# atmega16m1-breakout.net
KiCad netlist of a schematic drawn in EAGLE
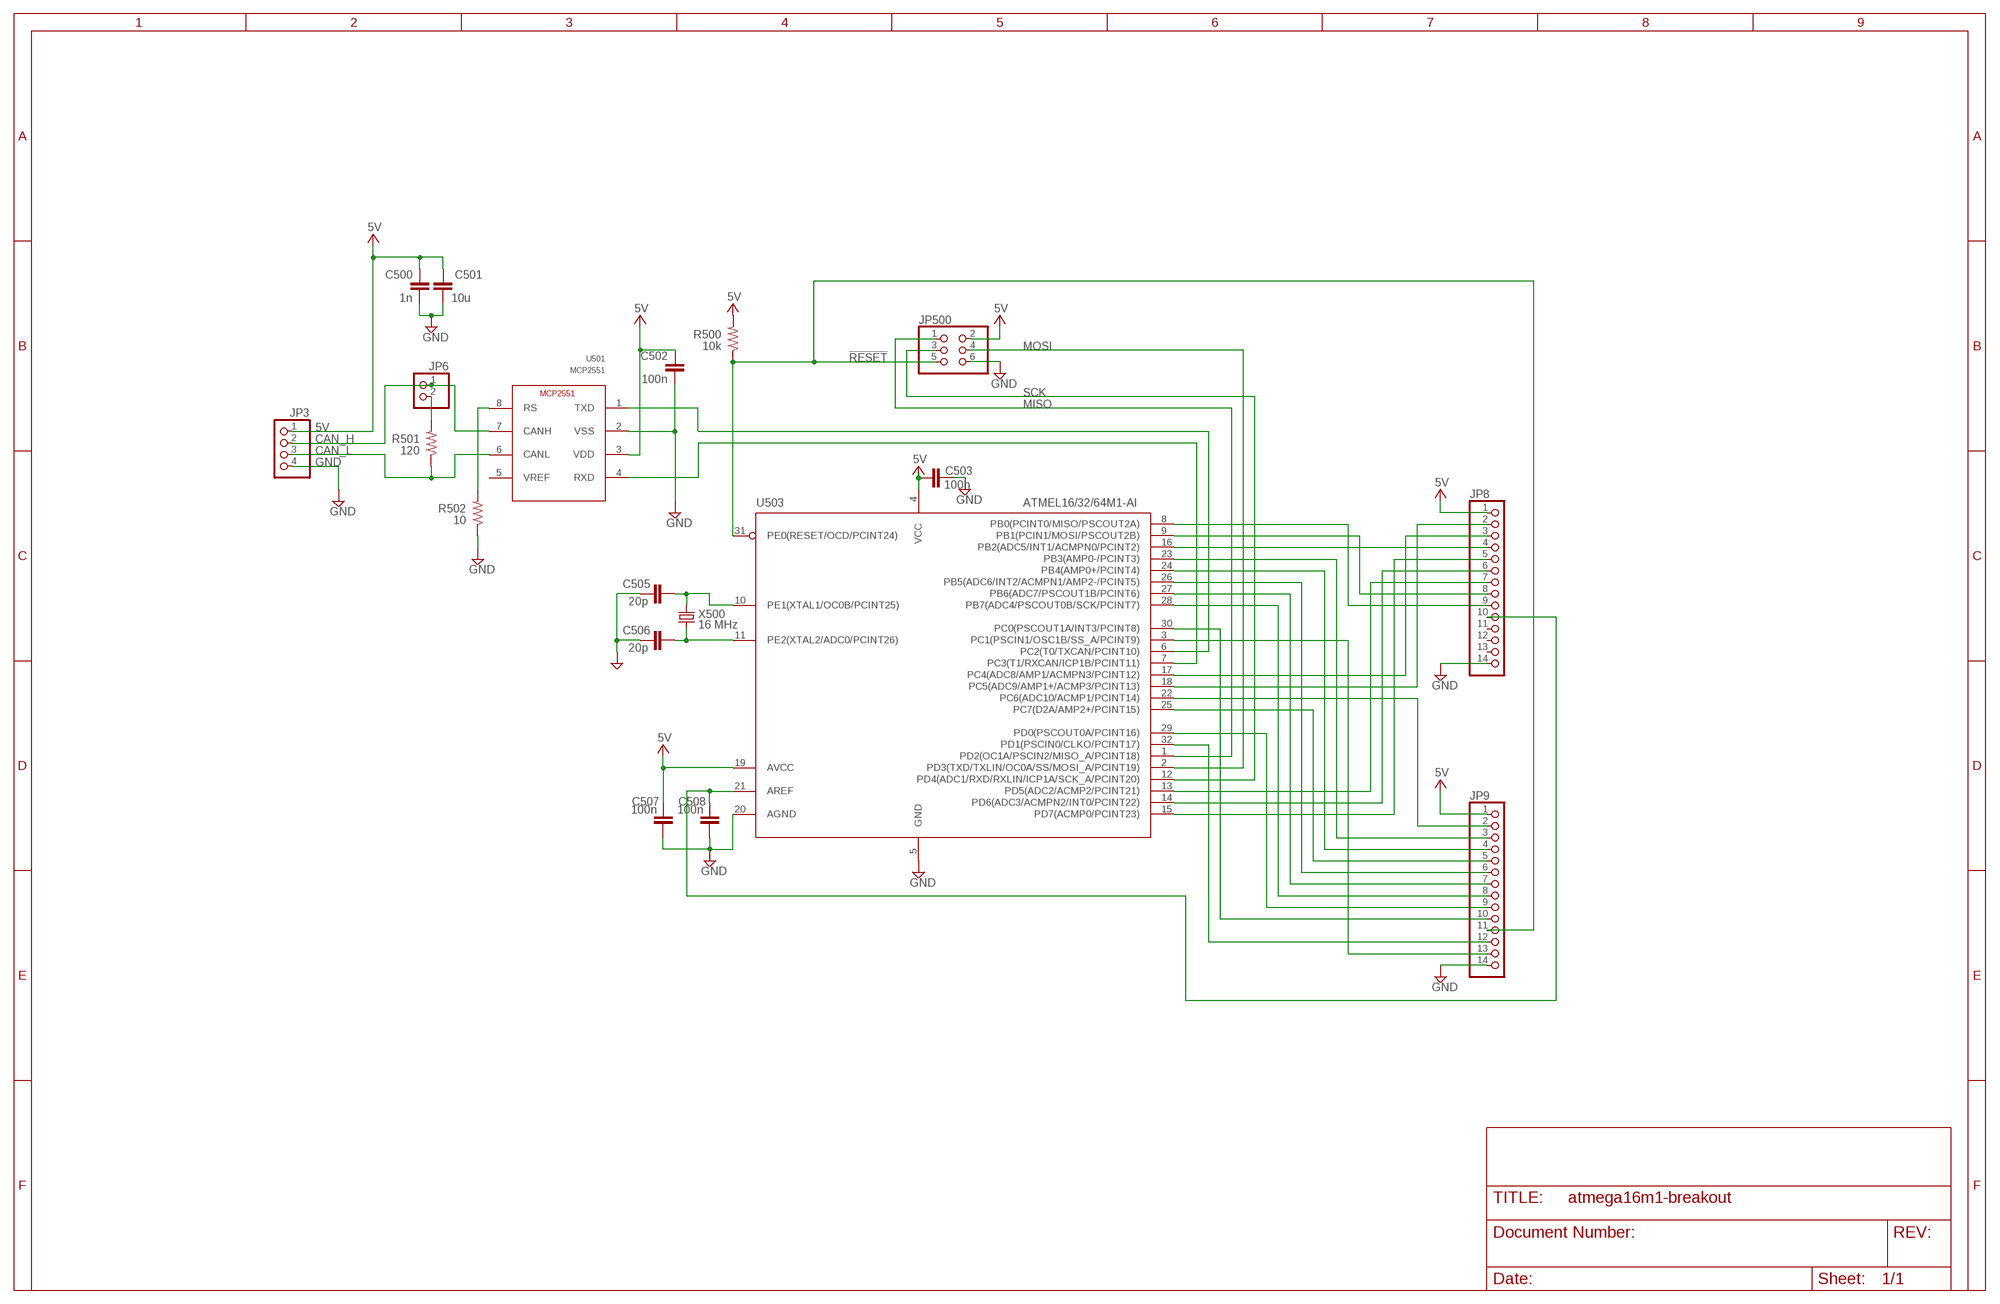
[diagram p0: schematic, sheet 1]

(export (version "E")
  (design (tool "Eeschema 10.0.6"))
  (components
    (comp (ref "C500")
      (value "1n")
      (footprint "eagle-import:0603-B-NOSILK")
      (libsource (lib "eagle-import") (part "C-EU0603-B-NOSILK"))
    )
    (comp (ref "C501")
      (value "10u")
      (footprint "eagle-import:0805-B-NOSILK")
      (libsource (lib "eagle-import") (part "C-EU0805-B-NOSILK"))
    )
    (comp (ref "C502")
      (value "100n")
      (footprint "eagle-import:0603-B-NOSILK")
      (libsource (lib "eagle-import") (part "C-EU0603-B-NOSILK"))
    )
    (comp (ref "C503")
      (value "100n")
      (footprint "eagle-import:0603-B-NOSILK")
      (libsource (lib "eagle-import") (part "C-EU0603-B-NOSILK"))
    )
    (comp (ref "C505")
      (value "20p")
      (footprint "eagle-import:0603-B-NOSILK")
      (libsource (lib "eagle-import") (part "C-EU0603-B-NOSILK"))
    )
    (comp (ref "C506")
      (value "20p")
      (footprint "eagle-import:0603-B-NOSILK")
      (libsource (lib "eagle-import") (part "C-EU0603-B-NOSILK"))
    )
    (comp (ref "C507")
      (value "100n")
      (footprint "eagle-import:0603-B-NOSILK")
      (libsource (lib "eagle-import") (part "C-EU0603-B-NOSILK"))
    )
    (comp (ref "C508")
      (value "100n")
      (footprint "eagle-import:0603-B-NOSILK")
      (libsource (lib "eagle-import") (part "C-EU0603-B-NOSILK"))
    )
    (comp (ref "JP3")
      (value "PINHD-1X4")
      (footprint "eagle-import:1X04")
      (libsource (lib "eagle-import") (part "PINHD-1X4"))
    )
    (comp (ref "JP6")
      (value "PINHD-1X2")
      (footprint "eagle-import:1X02")
      (libsource (lib "eagle-import") (part "PINHD-1X2"))
    )
    (comp (ref "JP8")
      (value "PINHD-1X14")
      (footprint "eagle-import:1X14")
      (libsource (lib "eagle-import") (part "PINHD-1X14"))
    )
    (comp (ref "JP9")
      (value "PINHD-1X14")
      (footprint "eagle-import:1X14")
      (libsource (lib "eagle-import") (part "PINHD-1X14"))
    )
    (comp (ref "JP500")
      (value "PINHD-2X3")
      (footprint "eagle-import:2X03")
      (libsource (lib "eagle-import") (part "PINHD-2X3"))
    )
    (comp (ref "R500")
      (value "10k")
      (footprint "eagle-import:0603-B-NOSILK")
      (libsource (lib "eagle-import") (part "R-US_0603-B-NOSILK"))
    )
    (comp (ref "R501")
      (value "120")
      (footprint "eagle-import:0603-B-NOSILK")
      (libsource (lib "eagle-import") (part "R-US_0603-B-NOSILK"))
    )
    (comp (ref "R502")
      (value "10")
      (footprint "eagle-import:0603-B-NOSILK")
      (libsource (lib "eagle-import") (part "R-US_0603-B-NOSILK"))
    )
    (comp (ref "U501")
      (value "MCP2551")
      (footprint "eagle-import:SO08")
      (libsource (lib "eagle-import") (part "MCP2551"))
    )
    (comp (ref "U503")
      (value "ATMEL16/32/64M1-AI")
      (footprint "eagle-import:TQFP32-08")
      (fields (field (name "MPN") "ATMEGA8-16AU"))
      (libsource (lib "eagle-import") (part "ATMEL16/32/64M1-AZ"))
    )
    (comp (ref "X500")
      (value "16 MHz")
      (footprint "eagle-import:ABM3")
      (libsource (lib "eagle-import") (part "CRYSTALABM3"))
    )
  )
  (nets
    (net (code "1") (name "/CAN_H") (class "Default")
      (node (ref "JP3") (pin "2") (pinfunction "2_2") (pintype "passive"))
      (node (ref "JP6") (pin "1") (pinfunction "1_1") (pintype "passive"))
      (node (ref "U501") (pin "7") (pinfunction "CANH_7") (pintype "bidirectional"))
    )
    (net (code "2") (name "/CAN_L") (class "Default")
      (node (ref "JP3") (pin "3") (pinfunction "3_3") (pintype "passive"))
      (node (ref "R501") (pin "1") (pinfunction "1_1") (pintype "passive"))
      (node (ref "U501") (pin "6") (pinfunction "CANL_6") (pintype "bidirectional"))
    )
    (net (code "3") (name "/MISO") (class "Default")
      (node (ref "JP500") (pin "1") (pinfunction "1_1") (pintype "passive"))
      (node (ref "U503") (pin "1") (pinfunction "PD2(OC1A/PSCIN2/MISO_A/PCINT18)_1") (pintype "bidirectional"))
    )
    (net (code "4") (name "/MOSI") (class "Default")
      (node (ref "JP500") (pin "4") (pinfunction "4_4") (pintype "passive"))
      (node (ref "U503") (pin "2") (pinfunction "PD3(TXD/TXLIN/OC0A/SS/MOSI_A/PCINT19)_2") (pintype "bidirectional"))
    )
    (net (code "5") (name "/SCK") (class "Default")
      (node (ref "JP500") (pin "3") (pinfunction "3_3") (pintype "passive"))
      (node (ref "U503") (pin "12") (pinfunction "PD4(ADC1/RXD/RXLIN/ICP1A/SCK_A/PCINT20)_12") (pintype "bidirectional"))
    )
    (net (code "6") (name "/~{RESET}") (class "Default")
      (node (ref "JP500") (pin "5") (pinfunction "5_5") (pintype "passive"))
      (node (ref "JP9") (pin "11") (pinfunction "11_11") (pintype "passive"))
      (node (ref "R500") (pin "1") (pinfunction "1_1") (pintype "passive"))
      (node (ref "U503") (pin "31") (pinfunction "PE0(RESET/OCD/PCINT24)_31") (pintype "bidirectional"))
    )
    (net (code "7") (name "5V") (class "Default")
      (node (ref "C500") (pin "1") (pinfunction "1_1") (pintype "passive"))
      (node (ref "C501") (pin "1") (pinfunction "1_1") (pintype "passive"))
      (node (ref "C502") (pin "1") (pinfunction "1_1") (pintype "passive"))
      (node (ref "C503") (pin "2") (pinfunction "2_2") (pintype "passive"))
      (node (ref "C507") (pin "1") (pinfunction "1_1") (pintype "passive"))
      (node (ref "JP3") (pin "1") (pinfunction "1_1") (pintype "passive"))
      (node (ref "JP500") (pin "2") (pinfunction "2_2") (pintype "passive"))
      (node (ref "JP8") (pin "1") (pinfunction "1_1") (pintype "passive"))
      (node (ref "JP9") (pin "1") (pinfunction "1_1") (pintype "passive"))
      (node (ref "R500") (pin "2") (pinfunction "2_2") (pintype "passive"))
      (node (ref "U501") (pin "3") (pinfunction "VDD_3") (pintype "power_in"))
      (node (ref "U503") (pin "19") (pinfunction "AVCC_19") (pintype "power_in"))
      (node (ref "U503") (pin "4") (pinfunction "VCC_4") (pintype "power_in"))
    )
    (net (code "8") (name "GND") (class "Default")
      (node (ref "C500") (pin "2") (pinfunction "2_2") (pintype "passive"))
      (node (ref "C501") (pin "2") (pinfunction "2_2") (pintype "passive"))
      (node (ref "C502") (pin "2") (pinfunction "2_2") (pintype "passive"))
      (node (ref "C503") (pin "1") (pinfunction "1_1") (pintype "passive"))
      (node (ref "C505") (pin "2") (pinfunction "2_2") (pintype "passive"))
      (node (ref "C506") (pin "2") (pinfunction "2_2") (pintype "passive"))
      (node (ref "C507") (pin "2") (pinfunction "2_2") (pintype "passive"))
      (node (ref "C508") (pin "2") (pinfunction "2_2") (pintype "passive"))
      (node (ref "JP3") (pin "4") (pinfunction "4_4") (pintype "passive"))
      (node (ref "JP500") (pin "6") (pinfunction "6_6") (pintype "passive"))
      (node (ref "JP8") (pin "14") (pinfunction "14_14") (pintype "passive"))
      (node (ref "JP9") (pin "14") (pinfunction "14_14") (pintype "passive"))
      (node (ref "R502") (pin "1") (pinfunction "1_1") (pintype "passive"))
      (node (ref "U501") (pin "2") (pinfunction "VSS_2") (pintype "power_in"))
      (node (ref "U503") (pin "20") (pinfunction "AGND_20") (pintype "power_in"))
      (node (ref "U503") (pin "5") (pinfunction "GND_5") (pintype "power_in"))
    )
    (net (code "9") (name "Net-(JP6-Pad2)") (class "Default")
      (node (ref "JP6") (pin "2") (pinfunction "2_2") (pintype "passive"))
      (node (ref "R501") (pin "2") (pinfunction "2_2") (pintype "passive"))
    )
    (net (code "10") (name "Net-(U501-RS)") (class "Default")
      (node (ref "R502") (pin "2") (pinfunction "2_2") (pintype "passive"))
      (node (ref "U501") (pin "8") (pinfunction "RS_8") (pintype "bidirectional"))
    )
    (net (code "11") (name "Net-(U501-RXD)") (class "Default")
      (node (ref "U501") (pin "4") (pinfunction "RXD_4") (pintype "bidirectional"))
      (node (ref "U503") (pin "7") (pinfunction "PC3(T1/RXCAN/ICP1B/PCINT11)_7") (pintype "bidirectional"))
    )
    (net (code "12") (name "Net-(U501-TXD)") (class "Default")
      (node (ref "U501") (pin "1") (pinfunction "TXD_1") (pintype "bidirectional"))
      (node (ref "U503") (pin "6") (pinfunction "PC2(T0/TXCAN/PCINT10)_6") (pintype "bidirectional"))
    )
    (net (code "13") (name "Net-(U503-AREF)") (class "Default")
      (node (ref "C508") (pin "1") (pinfunction "1_1") (pintype "passive"))
      (node (ref "JP8") (pin "10") (pinfunction "10_10") (pintype "passive"))
      (node (ref "U503") (pin "21") (pinfunction "AREF_21") (pintype "passive"))
    )
    (net (code "14") (name "Net-(U503-PB0(PCINT0{slash}MISO{slash}PSCOUT2A))") (class "Default")
      (node (ref "JP8") (pin "9") (pinfunction "9_9") (pintype "passive"))
      (node (ref "U503") (pin "8") (pinfunction "PB0(PCINT0/MISO/PSCOUT2A)_8") (pintype "bidirectional"))
    )
    (net (code "15") (name "Net-(U503-PB1(PCIN1{slash}MOSI{slash}PSCOUT2B))") (class "Default")
      (node (ref "JP8") (pin "8") (pinfunction "8_8") (pintype "passive"))
      (node (ref "U503") (pin "9") (pinfunction "PB1(PCIN1/MOSI/PSCOUT2B)_9") (pintype "bidirectional"))
    )
    (net (code "16") (name "Net-(U503-PB2(ADC5{slash}INT1{slash}ACMPN0{slash}PCINT2))") (class "Default")
      (node (ref "JP8") (pin "4") (pinfunction "4_4") (pintype "passive"))
      (node (ref "U503") (pin "16") (pinfunction "PB2(ADC5/INT1/ACMPN0/PCINT2)_16") (pintype "bidirectional"))
    )
    (net (code "17") (name "Net-(U503-PB3(AMP0-{slash}PCINT3))") (class "Default")
      (node (ref "JP9") (pin "3") (pinfunction "3_3") (pintype "passive"))
      (node (ref "U503") (pin "23") (pinfunction "PB3(AMP0-/PCINT3)_23") (pintype "bidirectional"))
    )
    (net (code "18") (name "Net-(U503-PB4(AMP0+{slash}PCINT4))") (class "Default")
      (node (ref "JP9") (pin "4") (pinfunction "4_4") (pintype "passive"))
      (node (ref "U503") (pin "24") (pinfunction "PB4(AMP0+/PCINT4)_24") (pintype "bidirectional"))
    )
    (net (code "19") (name "Net-(U503-PB5(ADC6{slash}INT2{slash}ACMPN1{slash}AMP2-{slash}PCINT5))") (class "Default")
      (node (ref "JP9") (pin "6") (pinfunction "6_6") (pintype "passive"))
      (node (ref "U503") (pin "26") (pinfunction "PB5(ADC6/INT2/ACMPN1/AMP2-/PCINT5)_26") (pintype "bidirectional"))
    )
    (net (code "20") (name "Net-(U503-PB6(ADC7{slash}PSCOUT1B{slash}PCINT6))") (class "Default")
      (node (ref "JP9") (pin "7") (pinfunction "7_7") (pintype "passive"))
      (node (ref "U503") (pin "27") (pinfunction "PB6(ADC7/PSCOUT1B/PCINT6)_27") (pintype "bidirectional"))
    )
    (net (code "21") (name "Net-(U503-PB7(ADC4{slash}PSCOUT0B{slash}SCK{slash}PCINT7))") (class "Default")
      (node (ref "JP9") (pin "8") (pinfunction "8_8") (pintype "passive"))
      (node (ref "U503") (pin "28") (pinfunction "PB7(ADC4/PSCOUT0B/SCK/PCINT7)_28") (pintype "bidirectional"))
    )
    (net (code "22") (name "Net-(U503-PC0(PSCOUT1A{slash}INT3{slash}PCINT8))") (class "Default")
      (node (ref "JP9") (pin "10") (pinfunction "10_10") (pintype "passive"))
      (node (ref "U503") (pin "30") (pinfunction "PC0(PSCOUT1A/INT3/PCINT8)_30") (pintype "bidirectional"))
    )
    (net (code "23") (name "Net-(U503-PC1(PSCIN1{slash}OSC1B{slash}SS_A{slash}PCINT9))") (class "Default")
      (node (ref "JP9") (pin "13") (pinfunction "13_13") (pintype "passive"))
      (node (ref "U503") (pin "3") (pinfunction "PC1(PSCIN1/OSC1B/SS_A/PCINT9)_3") (pintype "bidirectional"))
    )
    (net (code "24") (name "Net-(U503-PC4(ADC8{slash}AMP1{slash}ACMPN3{slash}PCINT12))") (class "Default")
      (node (ref "JP8") (pin "3") (pinfunction "3_3") (pintype "passive"))
      (node (ref "U503") (pin "17") (pinfunction "PC4(ADC8/AMP1/ACMPN3/PCINT12)_17") (pintype "bidirectional"))
    )
    (net (code "25") (name "Net-(U503-PC5(ADC9{slash}AMP1+{slash}ACMP3{slash}PCINT13))") (class "Default")
      (node (ref "JP8") (pin "2") (pinfunction "2_2") (pintype "passive"))
      (node (ref "U503") (pin "18") (pinfunction "PC5(ADC9/AMP1+/ACMP3/PCINT13)_18") (pintype "bidirectional"))
    )
    (net (code "26") (name "Net-(U503-PC6(ADC10{slash}ACMP1{slash}PCINT14))") (class "Default")
      (node (ref "JP9") (pin "2") (pinfunction "2_2") (pintype "passive"))
      (node (ref "U503") (pin "22") (pinfunction "PC6(ADC10/ACMP1/PCINT14)_22") (pintype "bidirectional"))
    )
    (net (code "27") (name "Net-(U503-PC7(D2A{slash}AMP2+{slash}PCINT15))") (class "Default")
      (node (ref "JP9") (pin "5") (pinfunction "5_5") (pintype "passive"))
      (node (ref "U503") (pin "25") (pinfunction "PC7(D2A/AMP2+/PCINT15)_25") (pintype "bidirectional"))
    )
    (net (code "28") (name "Net-(U503-PD0(PSCOUT0A{slash}PCINT16))") (class "Default")
      (node (ref "JP9") (pin "9") (pinfunction "9_9") (pintype "passive"))
      (node (ref "U503") (pin "29") (pinfunction "PD0(PSCOUT0A/PCINT16)_29") (pintype "bidirectional"))
    )
    (net (code "29") (name "Net-(U503-PD1(PSCIN0{slash}CLKO{slash}PCINT17))") (class "Default")
      (node (ref "JP9") (pin "12") (pinfunction "12_12") (pintype "passive"))
      (node (ref "U503") (pin "32") (pinfunction "PD1(PSCIN0/CLKO/PCINT17)_32") (pintype "bidirectional"))
    )
    (net (code "30") (name "Net-(U503-PD5(ADC2{slash}ACMP2{slash}PCINT21))") (class "Default")
      (node (ref "JP8") (pin "7") (pinfunction "7_7") (pintype "passive"))
      (node (ref "U503") (pin "13") (pinfunction "PD5(ADC2/ACMP2/PCINT21)_13") (pintype "bidirectional"))
    )
    (net (code "31") (name "Net-(U503-PD6(ADC3{slash}ACMPN2{slash}INT0{slash}PCINT22))") (class "Default")
      (node (ref "JP8") (pin "6") (pinfunction "6_6") (pintype "passive"))
      (node (ref "U503") (pin "14") (pinfunction "PD6(ADC3/ACMPN2/INT0/PCINT22)_14") (pintype "bidirectional"))
    )
    (net (code "32") (name "Net-(U503-PD7(ACMP0{slash}PCINT23))") (class "Default")
      (node (ref "JP8") (pin "5") (pinfunction "5_5") (pintype "passive"))
      (node (ref "U503") (pin "15") (pinfunction "PD7(ACMP0/PCINT23)_15") (pintype "bidirectional"))
    )
    (net (code "33") (name "Net-(U503-PE1(XTAL1{slash}OC0B{slash}PCINT25))") (class "Default")
      (node (ref "C505") (pin "1") (pinfunction "1_1") (pintype "passive"))
      (node (ref "U503") (pin "10") (pinfunction "PE1(XTAL1/OC0B/PCINT25)_10") (pintype "bidirectional"))
      (node (ref "X500") (pin "P2") (pinfunction "2_P2") (pintype "passive"))
    )
    (net (code "34") (name "Net-(U503-PE2(XTAL2{slash}ADC0{slash}PCINT26))") (class "Default")
      (node (ref "C506") (pin "1") (pinfunction "1_1") (pintype "passive"))
      (node (ref "U503") (pin "11") (pinfunction "PE2(XTAL2/ADC0/PCINT26)_11") (pintype "bidirectional"))
      (node (ref "X500") (pin "P1") (pinfunction "1_P1") (pintype "passive"))
    )
    (net (code "35") (name "unconnected-(JP8-Pad11)") (class "Default")
      (node (ref "JP8") (pin "11") (pinfunction "11_11") (pintype "passive"))
    )
    (net (code "36") (name "unconnected-(JP8-Pad12)") (class "Default")
      (node (ref "JP8") (pin "12") (pinfunction "12_12") (pintype "passive"))
    )
    (net (code "37") (name "unconnected-(JP8-Pad13)") (class "Default")
      (node (ref "JP8") (pin "13") (pinfunction "13_13") (pintype "passive"))
    )
    (net (code "38") (name "unconnected-(U501-VREF-Pad5)") (class "Default")
      (node (ref "U501") (pin "5") (pinfunction "VREF_5") (pintype "bidirectional"))
    )
  )
)
